# NANDGATE.net
KiCad netlist of a schematic drawn in EAGLE
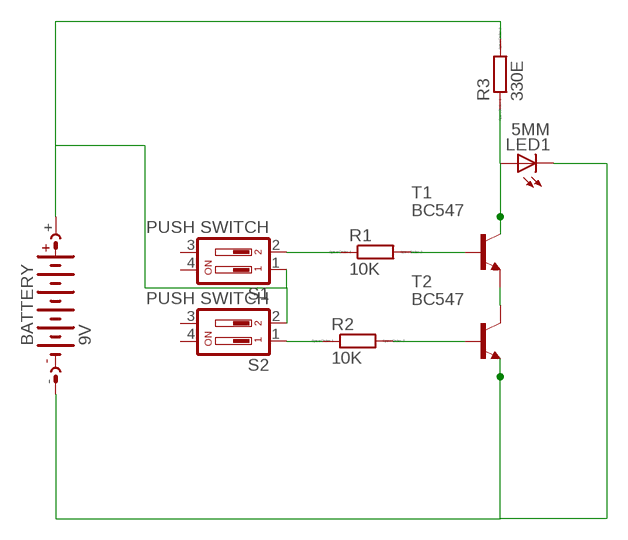
[diagram p0: schematic, sheet 1]

(export (version "E")
  (design (tool "Eeschema 10.0.6"))
  (components
    (comp (ref "BATTERY")
      (value "9V")
      (footprint "eagle-import:AB9V")
      (libsource (lib "eagle-import") (part "AB9V"))
    )
    (comp (ref "LED1")
      (value "5MM")
      (footprint "eagle-import:LED5MM")
      (libsource (lib "eagle-import") (part "LED5MM"))
    )
    (comp (ref "R1")
      (value "10K")
      (footprint "eagle-import:0204_7")
      (libsource (lib "eagle-import") (part "R0204/7"))
    )
    (comp (ref "R2")
      (value "10K")
      (footprint "eagle-import:0204_7")
      (libsource (lib "eagle-import") (part "R0204/7"))
    )
    (comp (ref "R3")
      (value "330E")
      (footprint "eagle-import:0204_7")
      (libsource (lib "eagle-import") (part "R0204/7"))
    )
    (comp (ref "S1")
      (value "PUSH SWITCH")
      (footprint "eagle-import:DS-02")
      (libsource (lib "eagle-import") (part "DS02"))
    )
    (comp (ref "S2")
      (value "PUSH SWITCH")
      (footprint "eagle-import:DS-02")
      (libsource (lib "eagle-import") (part "DS02"))
    )
    (comp (ref "T1")
      (value "BC547")
      (footprint "eagle-import:TO92")
      (libsource (lib "eagle-import") (part "BC547"))
    )
    (comp (ref "T2")
      (value "BC547")
      (footprint "eagle-import:TO92")
      (libsource (lib "eagle-import") (part "BC547"))
    )
  )
  (nets
    (net (code "1") (name "Net-(BATTERY-Pad+)") (class "Default")
      (node (ref "BATTERY") (pin "+") (pinfunction "+_+") (pintype "passive"))
      (node (ref "R3") (pin "2") (pinfunction "2_2") (pintype "passive"))
      (node (ref "S1") (pin "1") (pinfunction "1_1") (pintype "passive"))
      (node (ref "S2") (pin "2") (pinfunction "2_2") (pintype "passive"))
    )
    (net (code "2") (name "Net-(LED1-C)") (class "Default")
      (node (ref "BATTERY") (pin "-") (pinfunction "-_-") (pintype "passive"))
      (node (ref "LED1") (pin "K") (pinfunction "C_K") (pintype "passive"))
      (node (ref "T2") (pin "1") (pinfunction "E_1") (pintype "passive"))
    )
    (net (code "3") (name "Net-(R1-Pad1)") (class "Default")
      (node (ref "R1") (pin "1") (pinfunction "1_1") (pintype "passive"))
      (node (ref "S1") (pin "2") (pinfunction "2_2") (pintype "passive"))
    )
    (net (code "4") (name "Net-(R2-Pad1)") (class "Default")
      (node (ref "R2") (pin "1") (pinfunction "1_1") (pintype "passive"))
      (node (ref "S2") (pin "1") (pinfunction "1_1") (pintype "passive"))
    )
    (net (code "5") (name "Net-(T1-B)") (class "Default")
      (node (ref "R1") (pin "2") (pinfunction "2_2") (pintype "passive"))
      (node (ref "T1") (pin "2") (pinfunction "B_2") (pintype "passive"))
    )
    (net (code "6") (name "Net-(T1-C)") (class "Default")
      (node (ref "LED1") (pin "A") (pinfunction "A_A") (pintype "passive"))
      (node (ref "R3") (pin "1") (pinfunction "1_1") (pintype "passive"))
      (node (ref "T1") (pin "3") (pinfunction "C_3") (pintype "passive"))
    )
    (net (code "7") (name "Net-(T1-E)") (class "Default")
      (node (ref "T1") (pin "1") (pinfunction "E_1") (pintype "passive"))
      (node (ref "T2") (pin "3") (pinfunction "C_3") (pintype "passive"))
    )
    (net (code "8") (name "Net-(T2-B)") (class "Default")
      (node (ref "R2") (pin "2") (pinfunction "2_2") (pintype "passive"))
      (node (ref "T2") (pin "2") (pinfunction "B_2") (pintype "passive"))
    )
    (net (code "9") (name "unconnected-(S1-Pad3)") (class "Default")
      (node (ref "S1") (pin "3") (pinfunction "3_3") (pintype "passive"))
    )
    (net (code "10") (name "unconnected-(S1-Pad4)") (class "Default")
      (node (ref "S1") (pin "4") (pinfunction "4_4") (pintype "passive"))
    )
    (net (code "11") (name "unconnected-(S2-Pad3)") (class "Default")
      (node (ref "S2") (pin "3") (pinfunction "3_3") (pintype "passive"))
    )
    (net (code "12") (name "unconnected-(S2-Pad4)") (class "Default")
      (node (ref "S2") (pin "4") (pinfunction "4_4") (pintype "passive"))
    )
  )
)
